# MotionSensorEasyEDA.net
KiCad netlist of a schematic drawn in Altium Designer
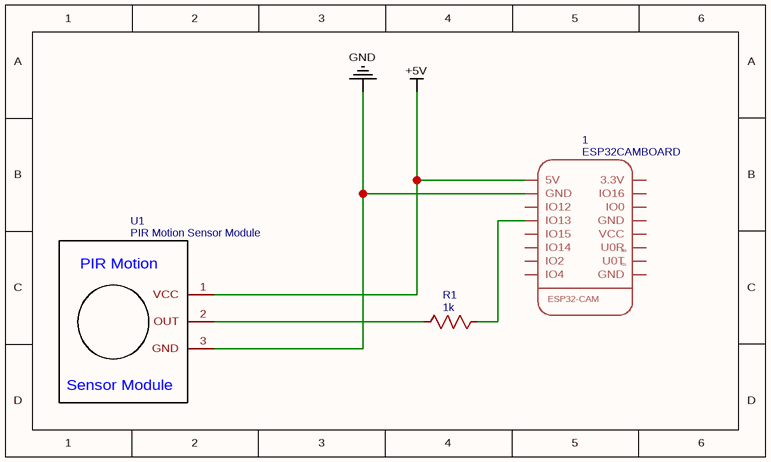
[diagram p0: MotionSensorEasyEDA.schdoc]

(export (version "E")
  (design (tool "Eeschema 10.0.6"))
  (components
    (comp (ref "1")
      (value "ESP32CAMBOARD")
      (fields (field (name "CONTRIBUTOR") "sakuyaki"))
      (libsource (lib "altium-import") (part "root_0_ESP32CAMBOARD_"))
    )
    (comp (ref "R1")
      (value "1k")
      (fields (field (name "CONTRIBUTOR") "LCEDA_Lib"))
      (libsource (lib "altium-import") (part "root_0_1k_"))
    )
    (comp (ref "U1")
      (value "PIR Motion Sensor Module")
      (fields (field (name "CONTRIBUTOR") "Bradenjarvis2"))
      (libsource (lib "altium-import") (part "root_0_PIR Motion Sensor Module_"))
    )
  )
  (nets
    (net (code "1") (name "+5V") (class "Default")
      (node (ref "1") (pin "5V") (pinfunction "5V_5V") (pintype "passive"))
      (node (ref "U1") (pin "1") (pinfunction "VCC_1") (pintype "passive"))
    )
    (net (code "2") (name "GND") (class "Default")
      (node (ref "1") (pin "GND@1") (pinfunction "GND_GND@1") (pintype "passive"))
      (node (ref "U1") (pin "3") (pinfunction "GND_3") (pintype "passive"))
    )
    (net (code "3") (name "Net-(1-PadIO13)") (class "Default")
      (node (ref "1") (pin "IO13") (pinfunction "IO13_IO13") (pintype "passive"))
      (node (ref "R1") (pin "2") (pinfunction "2_2") (pintype "passive"))
    )
    (net (code "4") (name "Net-(U1-OUT)") (class "Default")
      (node (ref "R1") (pin "1") (pinfunction "1_1") (pintype "passive"))
      (node (ref "U1") (pin "2") (pinfunction "OUT_2") (pintype "passive"))
    )
    (net (code "5") (name "unconnected-(1-GND-PadGND@2)") (class "Default")
      (node (ref "1") (pin "GND@2") (pinfunction "GND_GND@2") (pintype "passive"))
    )
    (net (code "6") (name "unconnected-(1-GND-PadGND@3)") (class "Default")
      (node (ref "1") (pin "GND@3") (pinfunction "GND_GND@3") (pintype "passive"))
    )
    (net (code "7") (name "unconnected-(1-Pad3.3V)") (class "Default")
      (node (ref "1") (pin "3.3V") (pinfunction "3.3V_3.3V") (pintype "passive"))
    )
    (net (code "8") (name "unconnected-(1-PadIO0)") (class "Default")
      (node (ref "1") (pin "IO0") (pinfunction "IO0_IO0") (pintype "passive"))
    )
    (net (code "9") (name "unconnected-(1-PadIO2)") (class "Default")
      (node (ref "1") (pin "IO2") (pinfunction "IO2_IO2") (pintype "passive"))
    )
    (net (code "10") (name "unconnected-(1-PadIO4)") (class "Default")
      (node (ref "1") (pin "IO4") (pinfunction "IO4_IO4") (pintype "passive"))
    )
    (net (code "11") (name "unconnected-(1-PadIO12)") (class "Default")
      (node (ref "1") (pin "IO12") (pinfunction "IO12_IO12") (pintype "passive"))
    )
    (net (code "12") (name "unconnected-(1-PadIO14)") (class "Default")
      (node (ref "1") (pin "IO14") (pinfunction "IO14_IO14") (pintype "passive"))
    )
    (net (code "13") (name "unconnected-(1-PadIO15)") (class "Default")
      (node (ref "1") (pin "IO15") (pinfunction "IO15_IO15") (pintype "passive"))
    )
    (net (code "14") (name "unconnected-(1-PadIO16)") (class "Default")
      (node (ref "1") (pin "IO16") (pinfunction "IO16_IO16") (pintype "passive"))
    )
    (net (code "15") (name "unconnected-(1-PadVCC)") (class "Default")
      (node (ref "1") (pin "VCC") (pinfunction "VCC_VCC") (pintype "passive"))
    )
    (net (code "16") (name "unconnected-(1-U0R-PadUDR)") (class "Default")
      (node (ref "1") (pin "UDR") (pinfunction "U0R_UDR") (pintype "passive"))
    )
    (net (code "17") (name "unconnected-(1-U0T-PadUDT)") (class "Default")
      (node (ref "1") (pin "UDT") (pinfunction "U0T_UDT") (pintype "passive"))
    )
  )
)
